# transmitter_bc548_crystal.net
KiCad netlist of a schematic drawn in EAGLE
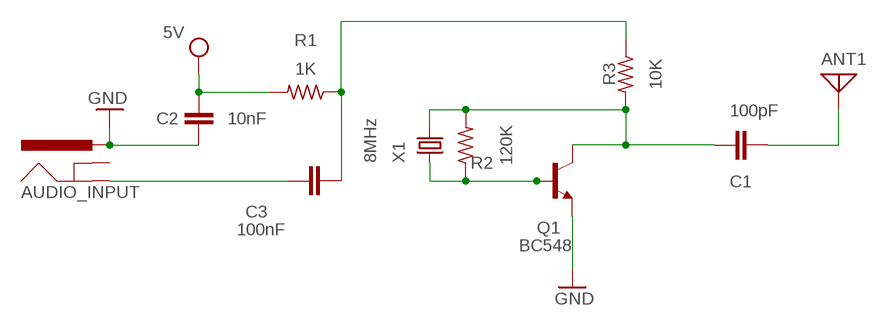
[diagram p0: schematic, sheet 1]

(export (version "E")
  (design (tool "Eeschema 10.0.6"))
  (components
    (comp (ref "ANT1")
      (value "ANTENNA")
      (footprint "eagle-import:PAD-01")
      (libsource (lib "eagle-import") (part "ANTENNA"))
    )
    (comp (ref "AUDIO_INPUT")
      (value "POWER_JACKPTH_SMD_COMBO")
      (footprint "eagle-import:POWER_JACK_COMBO")
      (libsource (lib "eagle-import") (part "POWER_JACKPTH_SMD_COMBO"))
    )
    (comp (ref "C1")
      (value "100pF")
      (footprint "eagle-import:XC10B6")
      (libsource (lib "eagle-import") (part "CXXC10B6"))
    )
    (comp (ref "C2")
      (value "10nF")
      (footprint "eagle-import:XC10B6")
      (libsource (lib "eagle-import") (part "CXXC10B6"))
    )
    (comp (ref "C3")
      (value "100nF")
      (footprint "eagle-import:XC10B6")
      (libsource (lib "eagle-import") (part "CXXC10B6"))
    )
    (comp (ref "Q1")
      (value "BC548")
      (footprint "eagle-import:TO92-EBC")
      (libsource (lib "eagle-import") (part "BC548"))
    )
    (comp (ref "R1")
      (value "1K")
      (footprint "eagle-import:RESAD724W46L381D178B")
      (libsource (lib "eagle-import") (part "R-USAXIAL-7.2MM-PITCH_"))
    )
    (comp (ref "R2")
      (value "120K")
      (footprint "eagle-import:RESAD724W46L381D178B")
      (libsource (lib "eagle-import") (part "R-USAXIAL-7.2MM-PITCH_"))
    )
    (comp (ref "R3")
      (value "10K")
      (footprint "eagle-import:RESAD724W46L381D178B")
      (libsource (lib "eagle-import") (part "R-USAXIAL-7.2MM-PITCH_"))
    )
    (comp (ref "X1")
      (value "8MHz")
      (footprint "eagle-import:86SMX")
      (libsource (lib "eagle-import") (part "CRYSTAL68SMX"))
    )
  )
  (nets
    (net (code "1") (name "GND") (class "Default")
      (node (ref "AUDIO_INPUT") (pin "POWER") (pinfunction "PWR_POWER") (pintype "bidirectional"))
      (node (ref "C2") (pin "2") (pinfunction "2_2") (pintype "passive"))
      (node (ref "Q1") (pin "E") (pinfunction "E_E") (pintype "passive"))
    )
    (net (code "2") (name "Net-(ANT1-Pad1)") (class "Default")
      (node (ref "ANT1") (pin "1") (pinfunction "1_1") (pintype "output"))
      (node (ref "C1") (pin "2") (pinfunction "2_2") (pintype "passive"))
    )
    (net (code "3") (name "Net-(AUDIO_INPUT-GND)") (class "Default")
      (node (ref "AUDIO_INPUT") (pin "GND@1") (pinfunction "GND_GND@1") (pintype "bidirectional"))
      (node (ref "C3") (pin "1") (pinfunction "1_1") (pintype "passive"))
    )
    (net (code "4") (name "Net-(C3-Pad2)") (class "Default")
      (node (ref "C3") (pin "2") (pinfunction "2_2") (pintype "passive"))
      (node (ref "R1") (pin "1") (pinfunction "1_1") (pintype "passive"))
      (node (ref "R3") (pin "1") (pinfunction "1_1") (pintype "passive"))
    )
    (net (code "5") (name "Net-(Q1-PadB)") (class "Default")
      (node (ref "Q1") (pin "B") (pinfunction "B_B") (pintype "passive"))
      (node (ref "R2") (pin "1") (pinfunction "1_1") (pintype "passive"))
      (node (ref "X1") (pin "1") (pinfunction "1_1") (pintype "passive"))
    )
    (net (code "6") (name "Net-(X1-2)") (class "Default")
      (node (ref "C1") (pin "1") (pinfunction "1_1") (pintype "passive"))
      (node (ref "Q1") (pin "C") (pinfunction "C_C") (pintype "passive"))
      (node (ref "R2") (pin "2") (pinfunction "2_2") (pintype "passive"))
      (node (ref "R3") (pin "2") (pinfunction "2_2") (pintype "passive"))
      (node (ref "X1") (pin "4") (pinfunction "2_4") (pintype "passive"))
    )
    (net (code "7") (name "VCC") (class "Default")
      (node (ref "C2") (pin "1") (pinfunction "1_1") (pintype "passive"))
      (node (ref "R1") (pin "2") (pinfunction "2_2") (pintype "passive"))
    )
    (net (code "8") (name "unconnected-(AUDIO_INPUT-GNDBREAK-PadGND)") (class "Default")
      (node (ref "AUDIO_INPUT") (pin "GND") (pinfunction "GNDBREAK_GND") (pintype "bidirectional"))
    )
  )
)
